# relflow_bed.net
KiCad netlist of a schematic drawn in Altium Designer
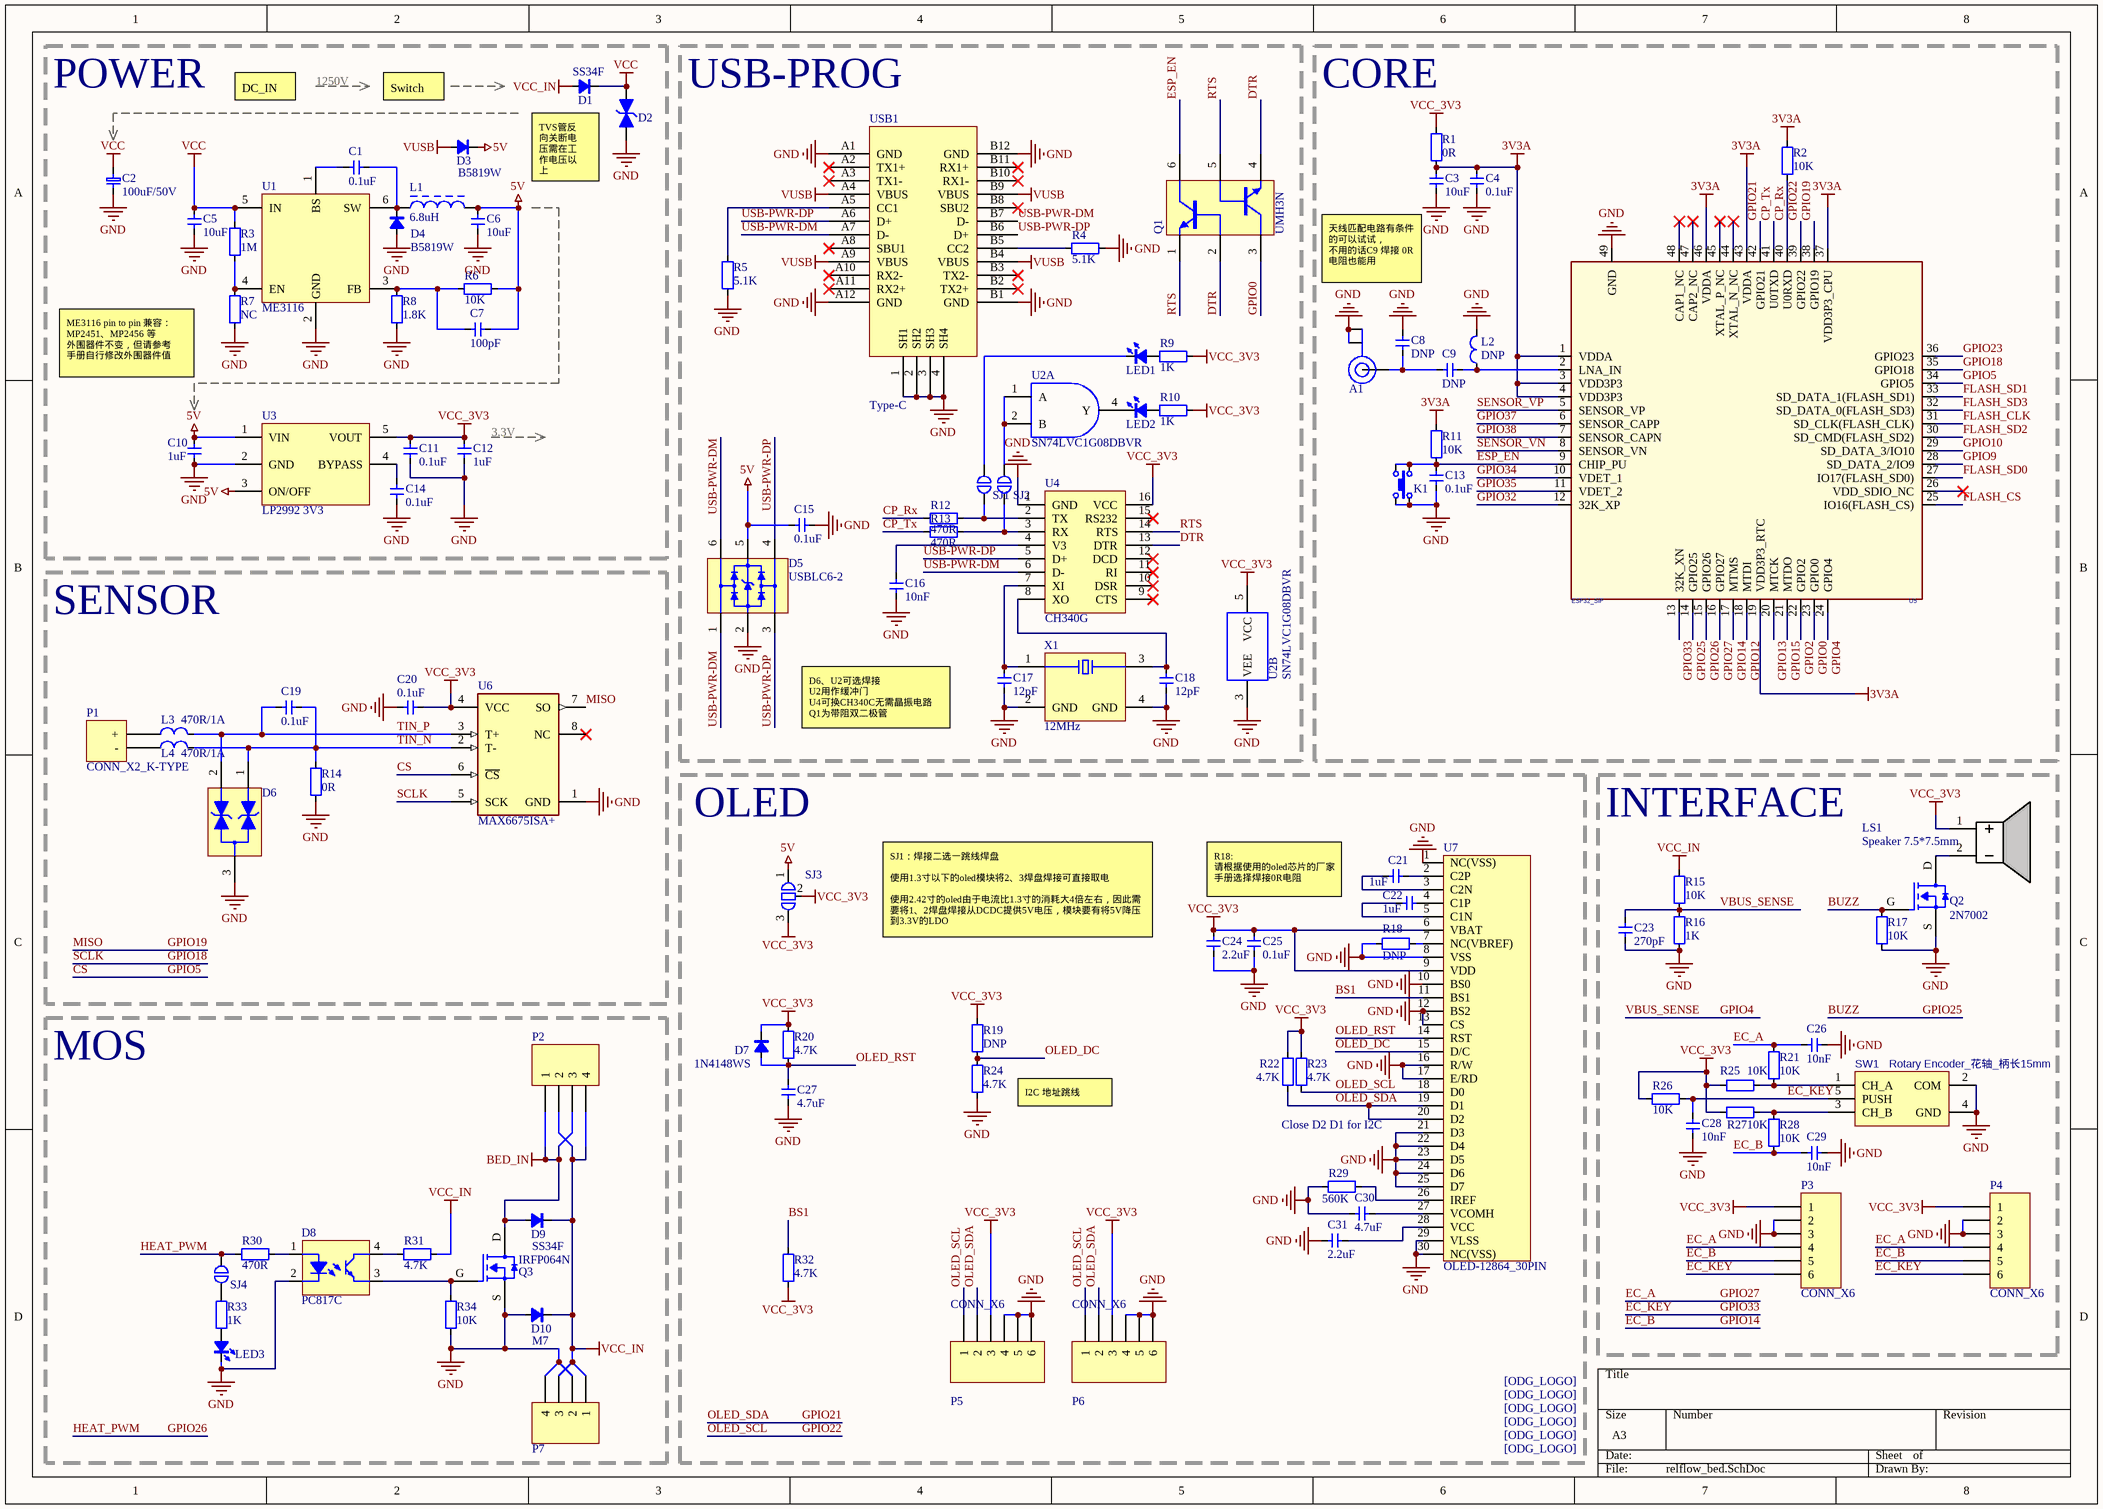
[diagram p0: relflow_bed.SchDoc]

(export (version "E")
  (design (tool "Eeschema 10.0.6"))
  (components
    (comp (ref "*1")
      (value "odg_logo")
      (footprint "odg_logo")
      (libsource (lib "relflow_bed") (part "odg_logo"))
    )
    (comp (ref "*2")
      (value "odg_logo")
      (footprint "odg_logo")
      (libsource (lib "relflow_bed") (part "odg_logo"))
    )
    (comp (ref "*3")
      (value "odg_logo")
      (footprint "odg_logo")
      (libsource (lib "relflow_bed") (part "odg_logo"))
    )
    (comp (ref "*4")
      (value "odg_logo")
      (footprint "odg_logo")
      (libsource (lib "relflow_bed") (part "odg_logo"))
    )
    (comp (ref "*5")
      (value "odg_logo")
      (footprint "odg_logo")
      (libsource (lib "relflow_bed") (part "odg_logo"))
    )
    (comp (ref "*6")
      (value "odg_logo")
      (footprint "odg_logo")
      (libsource (lib "relflow_bed") (part "odg_logo"))
    )
    (comp (ref "A1")
      (value "ANT_IPEX")
      (footprint "IPEX_SMD")
      (libsource (lib "relflow_bed") (part "ANT_IPEX"))
    )
    (comp (ref "C1")
      (value "0.1uF")
      (footprint "C0603")
      (description "Capacitor")
      (libsource (lib "relflow_bed") (part "CAP"))
    )
    (comp (ref "C2")
      (value "100uF/50V")
      (footprint "PANASONIC_E")
      (description "Capacitor")
      (libsource (lib "relflow_bed") (part "CAP_Polar"))
    )
    (comp (ref "C3")
      (value "10uF")
      (footprint "C0603")
      (description "Capacitor")
      (libsource (lib "relflow_bed") (part "CAP"))
    )
    (comp (ref "C4")
      (value "0.1uF")
      (footprint "C0603")
      (description "Capacitor")
      (libsource (lib "relflow_bed") (part "CAP"))
    )
    (comp (ref "C5")
      (value "10uF")
      (footprint "C1206")
      (description "Capacitor")
      (libsource (lib "relflow_bed") (part "CAP"))
    )
    (comp (ref "C6")
      (value "10uF")
      (footprint "C0805")
      (description "Capacitor")
      (libsource (lib "relflow_bed") (part "CAP"))
    )
    (comp (ref "C7")
      (value "100pF")
      (footprint "C0603")
      (description "Capacitor")
      (libsource (lib "relflow_bed") (part "CAP"))
    )
    (comp (ref "C8")
      (value "DNP")
      (footprint "C0603")
      (description "Capacitor")
      (libsource (lib "relflow_bed") (part "CAP"))
    )
    (comp (ref "C9")
      (value "DNP")
      (footprint "C0603")
      (description "Capacitor")
      (libsource (lib "relflow_bed") (part "CAP"))
    )
    (comp (ref "C10")
      (value "1uF")
      (footprint "C0603")
      (description "Capacitor")
      (libsource (lib "relflow_bed") (part "CAP"))
    )
    (comp (ref "C11")
      (value "0.1uF")
      (footprint "C0603")
      (description "Capacitor")
      (libsource (lib "relflow_bed") (part "CAP"))
    )
    (comp (ref "C12")
      (value "1uF")
      (footprint "C0603")
      (description "Capacitor")
      (libsource (lib "relflow_bed") (part "CAP"))
    )
    (comp (ref "C13")
      (value "0.1uF")
      (footprint "C0603")
      (description "Capacitor")
      (libsource (lib "relflow_bed") (part "CAP"))
    )
    (comp (ref "C14")
      (value "0.1uF")
      (footprint "C0603")
      (description "Capacitor")
      (libsource (lib "relflow_bed") (part "CAP"))
    )
    (comp (ref "C15")
      (value "0.1uF")
      (footprint "C0603")
      (description "Capacitor")
      (libsource (lib "relflow_bed") (part "CAP"))
    )
    (comp (ref "C16")
      (value "10nF")
      (footprint "C0603")
      (description "Capacitor")
      (libsource (lib "relflow_bed") (part "CAP"))
    )
    (comp (ref "C17")
      (value "12pF")
      (footprint "C0603")
      (description "Capacitor")
      (libsource (lib "relflow_bed") (part "CAP"))
    )
    (comp (ref "C18")
      (value "12pF")
      (footprint "C0603")
      (description "Capacitor")
      (libsource (lib "relflow_bed") (part "CAP"))
    )
    (comp (ref "C19")
      (value "0.1uF")
      (footprint "C0603")
      (description "Capacitor")
      (libsource (lib "relflow_bed") (part "CAP"))
    )
    (comp (ref "C20")
      (value "0.1uF")
      (footprint "C0603")
      (description "Capacitor")
      (libsource (lib "relflow_bed") (part "CAP"))
    )
    (comp (ref "C21")
      (value "1uF")
      (footprint "C0603")
      (description "Capacitor")
      (libsource (lib "relflow_bed") (part "CAP"))
    )
    (comp (ref "C22")
      (value "1uF")
      (footprint "C0603")
      (description "Capacitor")
      (libsource (lib "relflow_bed") (part "CAP"))
    )
    (comp (ref "C23")
      (value "270pF")
      (footprint "C0603")
      (description "Capacitor")
      (libsource (lib "relflow_bed") (part "CAP"))
    )
    (comp (ref "C24")
      (value "2.2uF")
      (footprint "C0603")
      (description "Capacitor")
      (libsource (lib "relflow_bed") (part "CAP"))
    )
    (comp (ref "C25")
      (value "0.1uF")
      (footprint "C0603")
      (description "Capacitor")
      (libsource (lib "relflow_bed") (part "CAP"))
    )
    (comp (ref "C26")
      (value "10nF")
      (footprint "C0603")
      (description "Capacitor")
      (libsource (lib "relflow_bed") (part "CAP"))
    )
    (comp (ref "C27")
      (value "4.7uF")
      (footprint "C0603")
      (description "Capacitor")
      (libsource (lib "relflow_bed") (part "CAP"))
    )
    (comp (ref "C28")
      (value "10nF")
      (footprint "C0603")
      (description "Capacitor")
      (libsource (lib "relflow_bed") (part "CAP"))
    )
    (comp (ref "C29")
      (value "10nF")
      (footprint "C0603")
      (description "Capacitor")
      (libsource (lib "relflow_bed") (part "CAP"))
    )
    (comp (ref "C30")
      (value "4.7uF")
      (footprint "C0603")
      (description "Capacitor")
      (libsource (lib "relflow_bed") (part "CAP"))
    )
    (comp (ref "C31")
      (value "2.2uF")
      (footprint "C0603")
      (description "Capacitor")
      (libsource (lib "relflow_bed") (part "CAP"))
    )
    (comp (ref "D1") (value "SS34F") (footprint "SMAF") (libsource (lib "") (part "DIODE_1")))
    (comp (ref "D2")
      (value "TVS_Bi")
      (footprint "DO-214AA_SMBJ")
      (libsource (lib "relflow_bed") (part "TVS_Bi"))
    )
    (comp (ref "D3") (value "B5819W") (footprint "SOD-123") (libsource (lib "") (part "DIODE_1")))
    (comp (ref "D4") (value "B5819W") (footprint "SOD-123") (libsource (lib "relflow_bed") (part "DIODE")))
    (comp (ref "D5")
      (value "USBLC6-2")
      (footprint "MICROCHIP SOT-23-6 M6")
      (description "Very low capacitance ESD protection")
      (libsource (lib "relflow_bed") (part "USBLC6-2"))
    )
    (comp (ref "D6")
      (value "NUP2105L")
      (footprint "INFINEON SOT-23-3")
      (libsource (lib "relflow_bed") (part "NUP2105L"))
    )
    (comp (ref "D7") (value "1N4148WS") (footprint "SOD-323") (libsource (lib "relflow_bed") (part "DIODE")))
    (comp (ref "D8")
      (value "PC817C")
      (footprint "DIP-4_SMD")
      (libsource (lib "relflow_bed") (part "Optoisolator"))
    )
    (comp (ref "D9") (value "SS34F") (footprint "SMAF") (libsource (lib "") (part "DIODE_1")))
    (comp (ref "D10") (value "M7") (footprint "SMAF") (libsource (lib "") (part "DIODE_1")))
    (comp (ref "K1")
      (value "~")
      (footprint "TACTILE_SWITCH_SMD_4X4MM")
      (description "Button")
      (libsource (lib "relflow_bed") (part "ButtonTACT"))
    )
    (comp (ref "L1")
      (value "6.8uH")
      (footprint "IND-30301X")
      (libsource (lib "relflow_bed") (part "Inductor"))
    )
    (comp (ref "L2") (value "DNP") (footprint "L0603") (libsource (lib "relflow_bed") (part "FUSE")))
    (comp (ref "L3") (value "470R/1A") (footprint "L0603") (libsource (lib "relflow_bed") (part "FUSE")))
    (comp (ref "L4") (value "470R/1A") (footprint "L0603") (libsource (lib "relflow_bed") (part "FUSE")))
    (comp (ref "LED1") (value "LED") (footprint "LED 0603_1608") (libsource (lib "relflow_bed") (part "LED")))
    (comp (ref "LED2") (value "LED") (footprint "LED 0603_1608") (libsource (lib "relflow_bed") (part "LED")))
    (comp (ref "LED3") (value "LED") (footprint "LED 0603_1608") (libsource (lib "relflow_bed") (part "LED")))
    (comp (ref "LS1")
      (value "Speaker 7.5*7.5mm")
      (footprint "BUZZER_7525")
      (description "Speaker")
      (libsource (lib "relflow_bed") (part "Speaker"))
    )
    (comp (ref "P1")
      (value "CONN_X2_K-TYPE")
      (footprint "K型热电偶连接器母座")
      (libsource (lib "relflow_bed") (part "CONN_X2_K-TYPE"))
    )
    (comp (ref "P2") (value "CONN_X4") (footprint "5569_4P_HOR_90") (libsource (lib "") (part "CONN_X4_1")))
    (comp (ref "P3")
      (value "CONN_X6")
      (footprint "简易牛角座直插_2x3P")
      (libsource (lib "relflow_bed") (part "CONN_X6"))
    )
    (comp (ref "P4")
      (value "CONN_X6")
      (footprint "简易牛角座直插_2x3P")
      (libsource (lib "relflow_bed") (part "CONN_X6"))
    )
    (comp (ref "P5") (value "CONN_X6") (footprint "简易牛角座直插_2x3P") (libsource (lib "") (part "CONN_X6_1")))
    (comp (ref "P6") (value "CONN_X6") (footprint "简易牛角座直插_2x3P") (libsource (lib "") (part "CONN_X6_1")))
    (comp (ref "P7")
      (value "CONN_X4")
      (footprint "5566_4P_VEC")
      (libsource (lib "relflow_bed") (part "CONN_X4"))
    )
    (comp (ref "Q1")
      (value "UMH3N")
      (footprint "ON SEMI SOT-363")
      (description "NPN型带阻双三极管\r\nNPN+NPN, SOT-363, Dual Digital Transistor (Bias Resistor Built-in Transistor)")
      (libsource (lib "relflow_bed") (part "UMH3N"))
    )
    (comp (ref "Q2")
      (value "2N7002")
      (footprint "INFINEON SOT-23-3")
      (description "N-MOS")
      (libsource (lib "relflow_bed") (part "N-MOS"))
    )
    (comp (ref "Q3")
      (value "IRFP064N")
      (footprint "TO-247AC+HEAT_SINK-TO220")
      (description "N-MOS")
      (libsource (lib "relflow_bed") (part "N-MOS"))
    )
    (comp (ref "R1")
      (value "0R")
      (footprint "R0603")
      (description "Resistor")
      (libsource (lib "relflow_bed") (part "RES"))
    )
    (comp (ref "R2")
      (value "10K")
      (footprint "R0603")
      (description "Resistor")
      (libsource (lib "") (part "RES_2"))
    )
    (comp (ref "R3")
      (value "1M")
      (footprint "R0603")
      (description "Resistor")
      (libsource (lib "relflow_bed") (part "RES"))
    )
    (comp (ref "R4")
      (value "5.1K")
      (footprint "R0603")
      (description "Resistor")
      (libsource (lib "") (part "RES_1"))
    )
    (comp (ref "R5")
      (value "5.1K")
      (footprint "R0603")
      (description "Resistor")
      (libsource (lib "relflow_bed") (part "RES"))
    )
    (comp (ref "R6")
      (value "10K")
      (footprint "R0603")
      (description "Resistor")
      (libsource (lib "") (part "RES_1"))
    )
    (comp (ref "R7")
      (value "NC")
      (footprint "R0603")
      (description "Resistor")
      (libsource (lib "relflow_bed") (part "RES"))
    )
    (comp (ref "R8")
      (value "1.8K")
      (footprint "R0603")
      (description "Resistor")
      (libsource (lib "") (part "RES_2"))
    )
    (comp (ref "R9")
      (value "1K")
      (footprint "R0603")
      (description "Resistor")
      (libsource (lib "") (part "RES_1"))
    )
    (comp (ref "R10")
      (value "1K")
      (footprint "R0603")
      (description "Resistor")
      (libsource (lib "") (part "RES_1"))
    )
    (comp (ref "R11")
      (value "10K")
      (footprint "R0603")
      (description "Resistor")
      (libsource (lib "relflow_bed") (part "RES"))
    )
    (comp (ref "R12")
      (value "470R")
      (footprint "R0603")
      (description "Resistor")
      (libsource (lib "") (part "RES_2"))
    )
    (comp (ref "R13")
      (value "470R")
      (footprint "R0603")
      (description "Resistor")
      (libsource (lib "") (part "RES_2"))
    )
    (comp (ref "R14")
      (value "0R")
      (footprint "R0603")
      (description "Resistor")
      (libsource (lib "") (part "RES_1"))
    )
    (comp (ref "R15")
      (value "10K")
      (footprint "R0603")
      (description "Resistor")
      (libsource (lib "relflow_bed") (part "RES"))
    )
    (comp (ref "R16")
      (value "1K")
      (footprint "R0603")
      (description "Resistor")
      (libsource (lib "relflow_bed") (part "RES"))
    )
    (comp (ref "R17")
      (value "10K")
      (footprint "R0603")
      (description "Resistor")
      (libsource (lib "") (part "RES_2"))
    )
    (comp (ref "R18")
      (value "DNP")
      (footprint "R0603")
      (description "Resistor")
      (libsource (lib "") (part "RES_1"))
    )
    (comp (ref "R19")
      (value "DNP")
      (footprint "R0603")
      (description "Resistor")
      (libsource (lib "") (part "RES_3"))
    )
    (comp (ref "R20")
      (value "4.7K")
      (footprint "R0603")
      (description "Resistor")
      (libsource (lib "") (part "RES_2"))
    )
    (comp (ref "R21")
      (value "10K")
      (footprint "R0603")
      (description "Resistor")
      (libsource (lib "relflow_bed") (part "RES"))
    )
    (comp (ref "R22")
      (value "4.7K")
      (footprint "R0603")
      (description "Resistor")
      (libsource (lib "relflow_bed") (part "RES"))
    )
    (comp (ref "R23")
      (value "4.7K")
      (footprint "R0603")
      (description "Resistor")
      (libsource (lib "relflow_bed") (part "RES"))
    )
    (comp (ref "R24")
      (value "4.7K")
      (footprint "R0603")
      (description "Resistor")
      (libsource (lib "") (part "RES_3"))
    )
    (comp (ref "R25")
      (value "10K")
      (footprint "R0603")
      (description "Resistor")
      (libsource (lib "") (part "RES_1"))
    )
    (comp (ref "R26")
      (value "10K")
      (footprint "R0603")
      (description "Resistor")
      (libsource (lib "") (part "RES_1"))
    )
    (comp (ref "R27")
      (value "10K")
      (footprint "R0603")
      (description "Resistor")
      (libsource (lib "") (part "RES_1"))
    )
    (comp (ref "R28")
      (value "10K")
      (footprint "R0603")
      (description "Resistor")
      (libsource (lib "relflow_bed") (part "RES"))
    )
    (comp (ref "R29")
      (value "560K")
      (footprint "R0603")
      (description "Resistor")
      (libsource (lib "") (part "RES_3"))
    )
    (comp (ref "R30")
      (value "470R")
      (footprint "R0603")
      (description "Resistor")
      (libsource (lib "relflow_bed") (part "RES"))
    )
    (comp (ref "R31")
      (value "4.7K")
      (footprint "R0603")
      (description "Resistor")
      (libsource (lib "relflow_bed") (part "RES"))
    )
    (comp (ref "R32")
      (value "4.7K")
      (footprint "R0603")
      (description "Resistor")
      (libsource (lib "") (part "RES_2"))
    )
    (comp (ref "R33")
      (value "1K")
      (footprint "R0603")
      (description "Resistor")
      (libsource (lib "") (part "RES_1"))
    )
    (comp (ref "R34")
      (value "10K")
      (footprint "R0603")
      (description "Resistor")
      (libsource (lib "") (part "RES_2"))
    )
    (comp (ref "SJ1") (value "SJ_2P") (footprint "SJ_2P_MINI") (libsource (lib "relflow_bed") (part "SJ_2P")))
    (comp (ref "SJ2") (value "SJ_2P") (footprint "SJ_2P_MINI") (libsource (lib "relflow_bed") (part "SJ_2P")))
    (comp (ref "SJ3") (value "SJ_3P") (footprint "SJ_3P") (libsource (lib "relflow_bed") (part "SJ_3P")))
    (comp (ref "SJ4") (value "SJ_2P") (footprint "SJ_2P_MINI") (libsource (lib "relflow_bed") (part "SJ_2P")))
    (comp (ref "SW1")
      (value "Rotary Encoder_花轴_柄长15mm")
      (footprint "ENCODER-1")
      (libsource (lib "relflow_bed") (part "Rotary Encoder"))
    )
    (comp (ref "U1")
      (value "ME3116")
      (footprint "MICROCHIP SOT-23-6 M6")
      (description "DC-DC")
      (libsource (lib "relflow_bed") (part "ME3116"))
    )
    (comp (ref "U2")
      (value "SN74LVC1G08DBVR")
      (footprint "MICROCHIP SOT-23-5 OT")
      (description "Single 2-input AND gate\r\n1.8~3.3V logic")
      (libsource (lib "relflow_bed") (part "SN74LVC1G08DBVR"))
    )
    (comp (ref "U3")
      (value "LP2992 3V3")
      (footprint "MICROCHIP SOT-23-5 OT")
      (description "LDO")
      (libsource (lib "relflow_bed") (part "LP2992"))
    )
    (comp (ref "U4")
      (value "CH340G")
      (footprint "TI SOP-16 D")
      (description "丐中丐，需要外接12M晶振")
      (libsource (lib "relflow_bed") (part "CH340G"))
    )
    (comp (ref "U5")
      (value "ESP32_SIP")
      (footprint "QFN-48_7X7_via")
      (libsource (lib "relflow_bed") (part "ESP32-PICO"))
    )
    (comp (ref "U6")
      (value "MAX6675ISA")
      (footprint "SO-8")
      (description "IC THERMOCOUP TO DGTL 8-SOIC")
      (fields
        (field (name "MANUFACTURER") "Maxim Electronics")
        (field (name "OCTOPART PART NUMBER") "33bcfab92ad8ec7b")
        (field (name "PART NUMBER") "MAX6675ISA+")
      )
      (libsource (lib "OpenHeat") (part "MAX6675ISA"))
    )
    (comp (ref "U7")
      (value "OLED-12864_30PIN")
      (footprint "UG-2864HSWEG01_1.29_SSD1315_BUTTOM")
      (description "显示屏")
      (libsource (lib "relflow_bed") (part "OLED-12864_30PIN"))
    )
    (comp (ref "USB1")
      (value "Type-C")
      (footprint "Type-C-TOP")
      (libsource (lib "relflow_bed") (part "USB-Type-C-24P"))
    )
    (comp (ref "X1")
      (value "12MHz")
      (footprint "EPSON TSX-3225")
      (description "4脚无源晶振")
      (libsource (lib "relflow_bed") (part "XTAL-4P"))
    )
  )
  (nets
    (net (code "1") (name "/BS1") (class "Default")
      (node (ref "R32") (pin "2") (pinfunction "2_2") (pintype "passive"))
      (node (ref "U7") (pin "11") (pinfunction "BS1_11") (pintype "passive"))
    )
    (net (code "2") (name "/BUZZ") (class "Default")
      (node (ref "Q2") (pin "G") (pinfunction "G_G") (pintype "passive"))
      (node (ref "R17") (pin "2") (pinfunction "2_2") (pintype "passive"))
      (node (ref "U5") (pin "14") (pinfunction "GPIO25_14") (pintype "passive"))
    )
    (net (code "3") (name "/CP_Rx") (class "Default")
      (node (ref "R12") (pin "1") (pinfunction "1_1") (pintype "passive"))
      (node (ref "R2") (pin "1") (pinfunction "1_1") (pintype "passive"))
      (node (ref "U5") (pin "40") (pinfunction "U0RXD_40") (pintype "power_in"))
    )
    (net (code "4") (name "/CP_Tx") (class "Default")
      (node (ref "R13") (pin "1") (pinfunction "1_1") (pintype "passive"))
      (node (ref "U5") (pin "41") (pinfunction "U0TXD_41") (pintype "power_in"))
    )
    (net (code "5") (name "/CS") (class "Default")
      (node (ref "U5") (pin "34") (pinfunction "GPIO5_34") (pintype "passive"))
      (node (ref "U6") (pin "6") (pinfunction "~{CS}_6") (pintype "input"))
    )
    (net (code "6") (name "/DTR") (class "Default")
      (node (ref "Q1") (pin "2") (pinfunction "B_2") (pintype "passive"))
      (node (ref "Q1") (pin "4") (pinfunction "E_4") (pintype "passive"))
      (node (ref "U4") (pin "13") (pinfunction "DTR_13") (pintype "passive"))
    )
    (net (code "7") (name "/EC_A") (class "Default")
      (node (ref "C26") (pin "2") (pinfunction "2_2") (pintype "passive"))
      (node (ref "P3") (pin "4") (pinfunction "4_4") (pintype "passive"))
      (node (ref "P4") (pin "4") (pinfunction "4_4") (pintype "passive"))
      (node (ref "R21") (pin "1") (pinfunction "1_1") (pintype "passive"))
      (node (ref "U5") (pin "16") (pinfunction "GPIO27_16") (pintype "passive"))
    )
    (net (code "8") (name "/EC_B") (class "Default")
      (node (ref "C29") (pin "2") (pinfunction "2_2") (pintype "passive"))
      (node (ref "P3") (pin "5") (pinfunction "5_5") (pintype "passive"))
      (node (ref "P4") (pin "5") (pinfunction "5_5") (pintype "passive"))
      (node (ref "R28") (pin "2") (pinfunction "2_2") (pintype "passive"))
      (node (ref "U5") (pin "17") (pinfunction "MTMS_17") (pintype "passive"))
    )
    (net (code "9") (name "/EC_KEY") (class "Default")
      (node (ref "C28") (pin "2") (pinfunction "2_2") (pintype "passive"))
      (node (ref "P3") (pin "6") (pinfunction "6_6") (pintype "passive"))
      (node (ref "P4") (pin "6") (pinfunction "6_6") (pintype "passive"))
      (node (ref "R26") (pin "1") (pinfunction "1_1") (pintype "passive"))
      (node (ref "SW1") (pin "5") (pinfunction "PUSH_5") (pintype "passive"))
      (node (ref "U5") (pin "13") (pinfunction "32K_XN_13") (pintype "passive"))
    )
    (net (code "10") (name "/ESP_EN") (class "Default")
      (node (ref "C13") (pin "1") (pinfunction "1_1") (pintype "passive"))
      (node (ref "K1") (pin "3") (pinfunction "3_3") (pintype "passive"))
      (node (ref "K1") (pin "4") (pinfunction "4_4") (pintype "passive"))
      (node (ref "Q1") (pin "6") (pinfunction "C_6") (pintype "passive"))
      (node (ref "R11") (pin "2") (pinfunction "2_2") (pintype "passive"))
      (node (ref "U5") (pin "9") (pinfunction "CHIP_PU_9") (pintype "passive"))
    )
    (net (code "11") (name "/FLASH_CLK") (class "Default")
      (node (ref "U5") (pin "31") (pinfunction "SD_CLK(FLASH_CLK)_31") (pintype "passive"))
    )
    (net (code "12") (name "/FLASH_CS") (class "Default")
      (node (ref "U5") (pin "25") (pinfunction "IO16(FLASH_CS)_25") (pintype "passive"))
    )
    (net (code "13") (name "/FLASH_SD0") (class "Default")
      (node (ref "U5") (pin "27") (pinfunction "IO17(FLASH_SD0)_27") (pintype "passive"))
    )
    (net (code "14") (name "/FLASH_SD1") (class "Default")
      (node (ref "U5") (pin "33") (pinfunction "SD_DATA_1(FLASH_SD1)_33") (pintype "passive"))
    )
    (net (code "15") (name "/FLASH_SD2") (class "Default")
      (node (ref "U5") (pin "30") (pinfunction "SD_CMD(FLASH_SD2)_30") (pintype "passive"))
    )
    (net (code "16") (name "/FLASH_SD3") (class "Default")
      (node (ref "U5") (pin "32") (pinfunction "SD_DATA_0(FLASH_SD3)_32") (pintype "passive"))
    )
    (net (code "17") (name "/GPIO0") (class "Default")
      (node (ref "Q1") (pin "3") (pinfunction "C_3") (pintype "passive"))
      (node (ref "U5") (pin "23") (pinfunction "GPIO0_23") (pintype "passive"))
    )
    (net (code "18") (name "/GPIO2") (class "Default")
      (node (ref "U5") (pin "22") (pinfunction "GPIO2_22") (pintype "passive"))
    )
    (net (code "19") (name "/GPIO4") (class "Default")
      (node (ref "C23") (pin "2") (pinfunction "2_2") (pintype "passive"))
      (node (ref "R15") (pin "2") (pinfunction "2_2") (pintype "passive"))
      (node (ref "R16") (pin "1") (pinfunction "1_1") (pintype "passive"))
      (node (ref "U5") (pin "24") (pinfunction "GPIO4_24") (pintype "passive"))
    )
    (net (code "20") (name "/GPIO9") (class "Default")
      (node (ref "U5") (pin "28") (pinfunction "SD_DATA_2/IO9_28") (pintype "passive"))
    )
    (net (code "21") (name "/GPIO10") (class "Default")
      (node (ref "U5") (pin "29") (pinfunction "SD_DATA_3/IO10_29") (pintype "passive"))
    )
    (net (code "22") (name "/GPIO12") (class "Default")
      (node (ref "U5") (pin "18") (pinfunction "MTDI_18") (pintype "passive"))
    )
    (net (code "23") (name "/GPIO13") (class "Default")
      (node (ref "U5") (pin "20") (pinfunction "MTCK_20") (pintype "passive"))
    )
    (net (code "24") (name "/GPIO15") (class "Default")
      (node (ref "U5") (pin "21") (pinfunction "MTDO_21") (pintype "passive"))
    )
    (net (code "25") (name "/GPIO18") (class "Default")
      (node (ref "U5") (pin "35") (pinfunction "GPIO18_35") (pintype "passive"))
      (node (ref "U6") (pin "5") (pinfunction "SCK_5") (pintype "input"))
    )
    (net (code "26") (name "/GPIO19") (class "Default")
      (node (ref "U5") (pin "38") (pinfunction "GPIO19_38") (pintype "passive"))
      (node (ref "U6") (pin "7") (pinfunction "SO_7") (pintype "output"))
    )
    (net (code "27") (name "/GPIO21") (class "Default")
      (node (ref "P5") (pin "2") (pinfunction "2_2") (pintype "passive"))
      (node (ref "P6") (pin "2") (pinfunction "2_2") (pintype "passive"))
      (node (ref "R22") (pin "2") (pinfunction "2_2") (pintype "passive"))
      (node (ref "U5") (pin "42") (pinfunction "GPIO21_42") (pintype "passive"))
      (node (ref "U7") (pin "19") (pinfunction "D1_19") (pintype "passive"))
      (node (ref "U7") (pin "20") (pinfunction "D2_20") (pintype "passive"))
    )
    (net (code "28") (name "/GPIO22") (class "Default")
      (node (ref "P5") (pin "1") (pinfunction "1_1") (pintype "passive"))
      (node (ref "P6") (pin "1") (pinfunction "1_1") (pintype "passive"))
      (node (ref "R23") (pin "2") (pinfunction "2_2") (pintype "passive"))
      (node (ref "U5") (pin "39") (pinfunction "GPIO22_39") (pintype "passive"))
      (node (ref "U7") (pin "18") (pinfunction "D0_18") (pintype "passive"))
    )
    (net (code "29") (name "/GPIO23") (class "Default")
      (node (ref "U5") (pin "36") (pinfunction "GPIO23_36") (pintype "passive"))
    )
    (net (code "30") (name "/GPIO26") (class "Default")
      (node (ref "R30") (pin "2") (pinfunction "2_2") (pintype "passive"))
      (node (ref "SJ4") (pin "1") (pinfunction "1_1") (pintype "passive"))
      (node (ref "U5") (pin "15") (pinfunction "GPIO26_15") (pintype "passive"))
    )
    (net (code "31") (name "/GPIO32") (class "Default")
      (node (ref "U5") (pin "12") (pinfunction "32K_XP_12") (pintype "passive"))
    )
    (net (code "32") (name "/GPIO34") (class "Default")
      (node (ref "U5") (pin "10") (pinfunction "VDET_1_10") (pintype "passive"))
    )
    (net (code "33") (name "/GPIO35") (class "Default")
      (node (ref "U5") (pin "11") (pinfunction "VDET_2_11") (pintype "passive"))
    )
    (net (code "34") (name "/GPIO37") (class "Default")
      (node (ref "U5") (pin "6") (pinfunction "SENSOR_CAPP_6") (pintype "passive"))
    )
    (net (code "35") (name "/GPIO38") (class "Default")
      (node (ref "U5") (pin "7") (pinfunction "SENSOR_CAPN_7") (pintype "passive"))
    )
    (net (code "36") (name "/OLED_DC") (class "Default")
      (node (ref "R19") (pin "1") (pinfunction "1_1") (pintype "passive"))
      (node (ref "R24") (pin "2") (pinfunction "2_2") (pintype "passive"))
      (node (ref "U7") (pin "15") (pinfunction "D/C_15") (pintype "passive"))
    )
    (net (code "37") (name "/OLED_RST") (class "Default")
      (node (ref "C27") (pin "2") (pinfunction "2_2") (pintype "passive"))
      (node (ref "D7") (pin "1") (pinfunction "A_1") (pintype "passive"))
      (node (ref "R20") (pin "1") (pinfunction "1_1") (pintype "passive"))
      (node (ref "U7") (pin "14") (pinfunction "RST_14") (pintype "passive"))
    )
    (net (code "38") (name "/RTS") (class "Default")
      (node (ref "Q1") (pin "1") (pinfunction "E_1") (pintype "passive"))
      (node (ref "Q1") (pin "5") (pinfunction "B_5") (pintype "passive"))
      (node (ref "U4") (pin "14") (pinfunction "RTS_14") (pintype "passive"))
    )
    (net (code "39") (name "/SENSOR_VN") (class "Default")
      (node (ref "U5") (pin "8") (pinfunction "SENSOR_VN_8") (pintype "passive"))
    )
    (net (code "40") (name "/SENSOR_VP") (class "Default")
      (node (ref "U5") (pin "5") (pinfunction "SENSOR_VP_5") (pintype "passive"))
    )
    (net (code "41") (name "/TIN_N") (class "Default")
      (node (ref "C19") (pin "1") (pinfunction "1_1") (pintype "passive"))
      (node (ref "D6") (pin "1") (pinfunction "1_1") (pintype "passive"))
      (node (ref "L4") (pin "2") (pinfunction "2_2") (pintype "passive"))
      (node (ref "R14") (pin "1") (pinfunction "1_1") (pintype "passive"))
      (node (ref "U6") (pin "2") (pinfunction "T-_2") (pintype "input"))
    )
    (net (code "42") (name "/TIN_P") (class "Default")
      (node (ref "C19") (pin "2") (pinfunction "2_2") (pintype "passive"))
      (node (ref "D6") (pin "2") (pinfunction "2_2") (pintype "passive"))
      (node (ref "L3") (pin "2") (pinfunction "2_2") (pintype "passive"))
      (node (ref "U6") (pin "3") (pinfunction "T+_3") (pintype "input"))
    )
    (net (code "43") (name "/USB-PWR-DM") (class "Default")
      (node (ref "D5") (pin "1") (pinfunction "I/O1_1") (pintype "passive"))
      (node (ref "D5") (pin "6") (pinfunction "I/O1_6") (pintype "passive"))
      (node (ref "U4") (pin "6") (pinfunction "D-_6") (pintype "passive"))
      (node (ref "USB1") (pin "A7") (pinfunction "D-_A7") (pintype "passive"))
      (node (ref "USB1") (pin "B7") (pinfunction "D-_B7") (pintype "passive"))
    )
    (net (code "44") (name "/USB-PWR-DP") (class "Default")
      (node (ref "D5") (pin "3") (pinfunction "I/O2_3") (pintype "passive"))
      (node (ref "D5") (pin "4") (pinfunction "I/O2_4") (pintype "passive"))
      (node (ref "U4") (pin "5") (pinfunction "D+_5") (pintype "passive"))
      (node (ref "USB1") (pin "A6") (pinfunction "D+_A6") (pintype "passive"))
      (node (ref "USB1") (pin "B6") (pinfunction "D+_B6") (pintype "passive"))
    )
    (net (code "45") (name "3V3A") (class "Default")
      (node (ref "C3") (pin "2") (pinfunction "2_2") (pintype "passive"))
      (node (ref "C4") (pin "2") (pinfunction "2_2") (pintype "passive"))
      (node (ref "R1") (pin "2") (pinfunction "2_2") (pintype "passive"))
      (node (ref "R11") (pin "1") (pinfunction "1_1") (pintype "passive"))
      (node (ref "R2") (pin "2") (pinfunction "2_2") (pintype "passive"))
      (node (ref "U5") (pin "1") (pinfunction "VDDA_1") (pintype "power_in"))
      (node (ref "U5") (pin "19") (pinfunction "VDD3P3_RTC_19") (pintype "power_in"))
      (node (ref "U5") (pin "3") (pinfunction "VDD3P3_3") (pintype "power_in"))
      (node (ref "U5") (pin "37") (pinfunction "VDD3P3_CPU_37") (pintype "power_in"))
      (node (ref "U5") (pin "4") (pinfunction "VDD3P3_4") (pintype "power_in"))
      (node (ref "U5") (pin "43") (pinfunction "VDDA_43") (pintype "power_in"))
      (node (ref "U5") (pin "46") (pinfunction "VDDA_46") (pintype "power_in"))
    )
    (net (code "46") (name "5V") (class "Default")
      (node (ref "C10") (pin "2") (pinfunction "2_2") (pintype "passive"))
      (node (ref "C15") (pin "2") (pinfunction "2_2") (pintype "passive"))
      (node (ref "C6") (pin "2") (pinfunction "2_2") (pintype "passive"))
      (node (ref "C7") (pin "2") (pinfunction "2_2") (pintype "passive"))
      (node (ref "D3") (pin "2") (pinfunction "C_2") (pintype "passive"))
      (node (ref "D5") (pin "5") (pinfunction "VBUS_5") (pintype "passive"))
      (node (ref "L1") (pin "2") (pinfunction "2_2") (pintype "passive"))
      (node (ref "R6") (pin "1") (pinfunction "1_1") (pintype "passive"))
      (node (ref "SJ3") (pin "1") (pinfunction "1_1") (pintype "passive"))
      (node (ref "U3") (pin "1") (pinfunction "VIN_1") (pintype "passive"))
      (node (ref "U3") (pin "3") (pinfunction "ON/OFF_3") (pintype "passive"))
    )
    (net (code "47") (name "BED_IN") (class "Default")
      (node (ref "D9") (pin "1") (pinfunction "A_1") (pintype "passive"))
      (node (ref "P2") (pin "1") (pinfunction "1_1") (pintype "passive"))
      (node (ref "P2") (pin "3") (pinfunction "3_3") (pintype "passive"))
      (node (ref "Q3") (pin "D") (pinfunction "D_D") (pintype "passive"))
    )
    (net (code "48") (name "GND") (class "Default")
      (node (ref "A1") (pin "2") (pinfunction "2_2") (pintype "passive"))
      (node (ref "A1") (pin "3") (pinfunction "3_3") (pintype "passive"))
      (node (ref "C10") (pin "1") (pinfunction "1_1") (pintype "passive"))
      (node (ref "C11") (pin "1") (pinfunction "1_1") (pintype "passive"))
      (node (ref "C12") (pin "1") (pinfunction "1_1") (pintype "passive"))
      (node (ref "C13") (pin "2") (pinfunction "2_2") (pintype "passive"))
      (node (ref "C14") (pin "1") (pinfunction "1_1") (pintype "passive"))
      (node (ref "C15") (pin "1") (pinfunction "1_1") (pintype "passive"))
      (node (ref "C16") (pin "1") (pinfunction "1_1") (pintype "passive"))
      (node (ref "C17") (pin "1") (pinfunction "1_1") (pintype "passive"))
      (node (ref "C18") (pin "1") (pinfunction "1_1") (pintype "passive"))
      (node (ref "C2") (pin "2") (pinfunction "2_2") (pintype "passive"))
      (node (ref "C20") (pin "2") (pinfunction "2_2") (pintype "passive"))
      (node (ref "C23") (pin "1") (pinfunction "1_1") (pintype "passive"))
      (node (ref "C24") (pin "1") (pinfunction "1_1") (pintype "passive"))
      (node (ref "C25") (pin "1") (pinfunction "1_1") (pintype "passive"))
      (node (ref "C26") (pin "1") (pinfunction "1_1") (pintype "passive"))
      (node (ref "C27") (pin "1") (pinfunction "1_1") (pintype "passive"))
      (node (ref "C28") (pin "1") (pinfunction "1_1") (pintype "passive"))
      (node (ref "C29") (pin "1") (pinfunction "1_1") (pintype "passive"))
      (node (ref "C3") (pin "1") (pinfunction "1_1") (pintype "passive"))
      (node (ref "C30") (pin "2") (pinfunction "2_2") (pintype "passive"))
      (node (ref "C31") (pin "2") (pinfunction "2_2") (pintype "passive"))
      (node (ref "C4") (pin "1") (pinfunction "1_1") (pintype "passive"))
      (node (ref "C5") (pin "2") (pinfunction "2_2") (pintype "passive"))
      (node (ref "C6") (pin "1") (pinfunction "1_1") (pintype "passive"))
      (node (ref "C8") (pin "2") (pinfunction "2_2") (pintype "passive"))
      (node (ref "D10") (pin "1") (pinfunction "A_1") (pintype "passive"))
      (node (ref "D2") (pin "1") (pinfunction "1_1") (pintype "passive"))
      (node (ref "D4") (pin "1") (pinfunction "A_1") (pintype "passive"))
      (node (ref "D5") (pin "2") (pinfunction "GND_2") (pintype "passive"))
      (node (ref "D6") (pin "3") (pinfunction "3_3") (pintype "passive"))
      (node (ref "D8") (pin "2") (pinfunction "2_2") (pintype "passive"))
      (node (ref "K1") (pin "1") (pinfunction "1_1") (pintype "passive"))
      (node (ref "K1") (pin "2") (pinfunction "2_2") (pintype "passive"))
      (node (ref "L2") (pin "2") (pinfunction "2_2") (pintype "passive"))
      (node (ref "LED3") (pin "2") (pinfunction "K_2") (pintype "passive"))
      (node (ref "P3") (pin "2") (pinfunction "2_2") (pintype "passive"))
      (node (ref "P3") (pin "3") (pinfunction "3_3") (pintype "passive"))
      (node (ref "P4") (pin "2") (pinfunction "2_2") (pintype "passive"))
      (node (ref "P4") (pin "3") (pinfunction "3_3") (pintype "passive"))
      (node (ref "P5") (pin "4") (pinfunction "4_4") (pintype "passive"))
      (node (ref "P5") (pin "5") (pinfunction "5_5") (pintype "passive"))
      (node (ref "P5") (pin "6") (pinfunction "6_6") (pintype "passive"))
      (node (ref "P6") (pin "4") (pinfunction "4_4") (pintype "passive"))
      (node (ref "P6") (pin "5") (pinfunction "5_5") (pintype "passive"))
      (node (ref "P6") (pin "6") (pinfunction "6_6") (pintype "passive"))
      (node (ref "P7") (pin "2") (pinfunction "2_2") (pintype "passive"))
      (node (ref "P7") (pin "4") (pinfunction "4_4") (pintype "passive"))
      (node (ref "Q2") (pin "S") (pinfunction "S_S") (pintype "passive"))
      (node (ref "Q3") (pin "S") (pinfunction "S_S") (pintype "passive"))
      (node (ref "R14") (pin "2") (pinfunction "2_2") (pintype "passive"))
      (node (ref "R16") (pin "2") (pinfunction "2_2") (pintype "passive"))
      (node (ref "R17") (pin "1") (pinfunction "1_1") (pintype "passive"))
      (node (ref "R18") (pin "2") (pinfunction "2_2") (pintype "passive"))
      (node (ref "R24") (pin "1") (pinfunction "1_1") (pintype "passive"))
      (node (ref "R29") (pin "1") (pinfunction "1_1") (pintype "passive"))
      (node (ref "R34") (pin "1") (pinfunction "1_1") (pintype "passive"))
      (node (ref "R4") (pin "1") (pinfunction "1_1") (pintype "passive"))
      (node (ref "R5") (pin "2") (pinfunction "2_2") (pintype "passive"))
      (node (ref "R7") (pin "2") (pinfunction "2_2") (pintype "passive"))
      (node (ref "R8") (pin "1") (pinfunction "1_1") (pintype "passive"))
      (node (ref "SW1") (pin "2") (pinfunction "COM_2") (pintype "passive"))
      (node (ref "SW1") (pin "4") (pinfunction "GND_4") (pintype "passive"))
      (node (ref "U1") (pin "2") (pinfunction "GND_2") (pintype "passive"))
      (node (ref "U2") (pin "3") (pinfunction "VEE_3") (pintype "passive"))
      (node (ref "U3") (pin "2") (pinfunction "GND_2") (pintype "passive"))
      (node (ref "U4") (pin "1") (pinfunction "GND_1") (pintype "passive"))
      (node (ref "U5") (pin "49") (pinfunction "GND_49") (pintype "power_in"))
      (node (ref "U6") (pin "1") (pinfunction "GND_1") (pintype "power_in"))
      (node (ref "U7") (pin "1") (pinfunction "NC(VSS)_1") (pintype "passive"))
      (node (ref "U7") (pin "10") (pinfunction "BS0_10") (pintype "passive"))
      (node (ref "U7") (pin "12") (pinfunction "BS2_12") (pintype "passive"))
      (node (ref "U7") (pin "13") (pinfunction "CS_13") (pintype "passive"))
      (node (ref "U7") (pin "16") (pinfunction "R/W_16") (pintype "passive"))
      (node (ref "U7") (pin "17") (pinfunction "E/RD_17") (pintype "passive"))
      (node (ref "U7") (pin "21") (pinfunction "D3_21") (pintype "passive"))
      (node (ref "U7") (pin "22") (pinfunction "D4_22") (pintype "passive"))
      (node (ref "U7") (pin "23") (pinfunction "D5_23") (pintype "passive"))
      (node (ref "U7") (pin "24") (pinfunction "D6_24") (pintype "passive"))
      (node (ref "U7") (pin "25") (pinfunction "D7_25") (pintype "passive"))
      (node (ref "U7") (pin "29") (pinfunction "VLSS_29") (pintype "passive"))
      (node (ref "U7") (pin "30") (pinfunction "NC(VSS)_30") (pintype "passive"))
      (node (ref "U7") (pin "8") (pinfunction "VSS_8") (pintype "passive"))
      (node (ref "USB1") (pin "1") (pinfunction "SH1_1") (pintype "passive"))
      (node (ref "USB1") (pin "2") (pinfunction "SH2_2") (pintype "passive"))
      (node (ref "USB1") (pin "3") (pinfunction "SH3_3") (pintype "passive"))
      (node (ref "USB1") (pin "4") (pinfunction "SH4_4") (pintype "passive"))
      (node (ref "USB1") (pin "A1") (pinfunction "GND_A1") (pintype "passive"))
      (node (ref "USB1") (pin "A12") (pinfunction "GND_A12") (pintype "passive"))
      (node (ref "USB1") (pin "B1") (pinfunction "GND_B1") (pintype "passive"))
      (node (ref "USB1") (pin "B12") (pinfunction "GND_B12") (pintype "passive"))
      (node (ref "X1") (pin "2") (pinfunction "GND_2") (pintype "passive"))
      (node (ref "X1") (pin "4") (pinfunction "GND_4") (pintype "passive"))
    )
    (net (code "49") (name "Net-(A1-Pad1)") (class "Default")
      (node (ref "A1") (pin "1") (pinfunction "1_1") (pintype "passive"))
      (node (ref "C8") (pin "1") (pinfunction "1_1") (pintype "passive"))
      (node (ref "C9") (pin "1") (pinfunction "1_1") (pintype "passive"))
    )
    (net (code "50") (name "Net-(D4-C)") (class "Default")
      (node (ref "C1") (pin "1") (pinfunction "1_1") (pintype "passive"))
      (node (ref "D4") (pin "2") (pinfunction "C_2") (pintype "passive"))
      (node (ref "L1") (pin "1") (pintype "passive"))
      (node (ref "U1") (pin "6") (pinfunction "SW_6") (pintype "passive"))
    )
    (net (code "51") (name "Net-(D8-Pad1)") (class "Default")
      (node (ref "D8") (pin "1") (pinfunction "1_1") (pintype "passive"))
      (node (ref "R30") (pin "1") (pinfunction "1_1") (pintype "passive"))
    )
    (net (code "52") (name "Net-(D8-Pad3)") (class "Default")
      (node (ref "D8") (pin "3") (pinfunction "3_3") (pintype "passive"))
      (node (ref "Q3") (pin "G") (pinfunction "G_G") (pintype "passive"))
      (node (ref "R34") (pin "2") (pinfunction "2_2") (pintype "passive"))
    )
    (net (code "53") (name "Net-(D8-Pad4)") (class "Default")
      (node (ref "D8") (pin "4") (pinfunction "4_4") (pintype "passive"))
      (node (ref "R31") (pin "2") (pinfunction "2_2") (pintype "passive"))
    )
    (net (code "54") (name "Net-(L3-Pad1)") (class "Default")
      (node (ref "L3") (pin "1") (pinfunction "1_1") (pintype "passive"))
      (node (ref "P1") (pin "+") (pinfunction "+_+") (pintype "passive"))
    )
    (net (code "55") (name "Net-(L4-Pad1)") (class "Default")
      (node (ref "L4") (pin "1") (pinfunction "1_1") (pintype "passive"))
      (node (ref "P1") (pin "-") (pinfunction "-_-") (pintype "passive"))
    )
    (net (code "56") (name "Net-(LED1-A)") (class "Default")
      (node (ref "LED1") (pin "1") (pinfunction "A_1") (pintype "passive"))
      (node (ref "R9") (pin "2") (pinfunction "2_2") (pintype "passive"))
    )
    (net (code "57") (name "Net-(LED1-K)") (class "Default")
      (node (ref "LED1") (pin "2") (pinfunction "K_2") (pintype "passive"))
      (node (ref "SJ1") (pin "1") (pinfunction "1_1") (pintype "passive"))
    )
    (net (code "58") (name "Net-(LED2-A)") (class "Default")
      (node (ref "LED2") (pin "1") (pinfunction "A_1") (pintype "passive"))
      (node (ref "R10") (pin "2") (pinfunction "2_2") (pintype "passive"))
    )
    (net (code "59") (name "Net-(LED2-K)") (class "Default")
      (node (ref "LED2") (pin "2") (pinfunction "K_2") (pintype "passive"))
      (node (ref "U2") (pin "4") (pinfunction "Y_4") (pintype "passive"))
    )
    (net (code "60") (name "Net-(LED3-A)") (class "Default")
      (node (ref "LED3") (pin "1") (pinfunction "A_1") (pintype "passive"))
      (node (ref "R33") (pin "2") (pinfunction "2_2") (pintype "passive"))
    )
    (net (code "61") (name "Net-(LS1--)") (class "Default")
      (node (ref "LS1") (pin "2") (pinfunction "-_2") (pintype "passive"))
      (node (ref "Q2") (pin "D") (pinfunction "D_D") (pintype "passive"))
    )
    (net (code "62") (name "Net-(R33-Pad1)") (class "Default")
      (node (ref "R33") (pin "1") (pinfunction "1_1") (pintype "passive"))
      (node (ref "SJ4") (pin "2") (pinfunction "2_2") (pintype "passive"))
    )
    (net (code "63") (name "Net-(SW1-CH_A)") (class "Default")
      (node (ref "R21") (pin "2") (pinfunction "2_2") (pintype "passive"))
      (node (ref "R25") (pin "1") (pinfunction "1_1") (pintype "passive"))
      (node (ref "SW1") (pin "1") (pinfunction "CH_A_1") (pintype "passive"))
    )
    (net (code "64") (name "Net-(SW1-CH_B)") (class "Default")
      (node (ref "R27") (pin "1") (pinfunction "1_1") (pintype "passive"))
      (node (ref "R28") (pin "1") (pinfunction "1_1") (pintype "passive"))
      (node (ref "SW1") (pin "3") (pinfunction "CH_B_3") (pintype "passive"))
    )
    (net (code "65") (name "Net-(U1-BS)") (class "Default")
      (node (ref "C1") (pin "2") (pinfunction "2_2") (pintype "passive"))
      (node (ref "U1") (pin "1") (pinfunction "BS_1") (pintype "passive"))
    )
    (net (code "66") (name "Net-(U1-EN)") (class "Default")
      (node (ref "R3") (pin "2") (pinfunction "2_2") (pintype "passive"))
      (node (ref "R7") (pin "1") (pinfunction "1_1") (pintype "passive"))
      (node (ref "U1") (pin "4") (pinfunction "EN_4") (pintype "passive"))
    )
    (net (code "67") (name "Net-(U1-FB)") (class "Default")
      (node (ref "C7") (pin "1") (pinfunction "1_1") (pintype "passive"))
      (node (ref "R6") (pin "2") (pinfunction "2_2") (pintype "passive"))
      (node (ref "R8") (pin "2") (pinfunction "2_2") (pintype "passive"))
      (node (ref "U1") (pin "3") (pinfunction "FB_3") (pintype "passive"))
    )
    (net (code "68") (name "Net-(U2A-A)") (class "Default")
      (node (ref "SJ2") (pin "1") (pinfunction "1_1") (pintype "passive"))
      (node (ref "U2") (pin "1") (pinfunction "A_1") (pintype "passive"))
      (node (ref "U2") (pin "2") (pinfunction "B_2") (pintype "passive"))
    )
    (net (code "69") (name "Net-(U3-BYPASS)") (class "Default")
      (node (ref "C14") (pin "2") (pinfunction "2_2") (pintype "passive"))
      (node (ref "U3") (pin "4") (pinfunction "BYPASS_4") (pintype "passive"))
    )
    (net (code "70") (name "Net-(U4-RX)") (class "Default")
      (node (ref "R13") (pin "2") (pinfunction "2_2") (pintype "passive"))
      (node (ref "SJ2") (pin "2") (pinfunction "2_2") (pintype "passive"))
      (node (ref "U4") (pin "3") (pinfunction "RX_3") (pintype "passive"))
    )
    (net (code "71") (name "Net-(U4-TX)") (class "Default")
      (node (ref "R12") (pin "2") (pinfunction "2_2") (pintype "passive"))
      (node (ref "SJ1") (pin "2") (pinfunction "2_2") (pintype "passive"))
      (node (ref "U4") (pin "2") (pinfunction "TX_2") (pintype "passive"))
    )
    (net (code "72") (name "Net-(U4-V3)") (class "Default")
      (node (ref "C16") (pin "2") (pinfunction "2_2") (pintype "passive"))
      (node (ref "U4") (pin "4") (pinfunction "V3_4") (pintype "passive"))
    )
    (net (code "73") (name "Net-(U4-XI)") (class "Default")
      (node (ref "C17") (pin "2") (pinfunction "2_2") (pintype "passive"))
      (node (ref "U4") (pin "7") (pinfunction "XI_7") (pintype "passive"))
      (node (ref "X1") (pin "1") (pinfunction "1_1") (pintype "passive"))
    )
    (net (code "74") (name "Net-(U4-XO)") (class "Default")
      (node (ref "C18") (pin "2") (pinfunction "2_2") (pintype "passive"))
      (node (ref "U4") (pin "8") (pinfunction "XO_8") (pintype "passive"))
      (node (ref "X1") (pin "3") (pinfunction "3_3") (pintype "passive"))
    )
    (net (code "75") (name "Net-(U5-LNA_IN)") (class "Default")
      (node (ref "C9") (pin "2") (pinfunction "2_2") (pintype "passive"))
      (node (ref "L2") (pin "1") (pinfunction "1_1") (pintype "passive"))
      (node (ref "U5") (pin "2") (pinfunction "LNA_IN_2") (pintype "passive"))
    )
    (net (code "76") (name "Net-(U7-C1N)") (class "Default")
      (node (ref "C22") (pin "2") (pinfunction "2_2") (pintype "passive"))
      (node (ref "U7") (pin "5") (pinfunction "C1N_5") (pintype "passive"))
    )
    (net (code "77") (name "Net-(U7-C1P)") (class "Default")
      (node (ref "C22") (pin "1") (pinfunction "1_1") (pintype "passive"))
      (node (ref "U7") (pin "4") (pinfunction "C1P_4") (pintype "passive"))
    )
    (net (code "78") (name "Net-(U7-C2N)") (class "Default")
      (node (ref "C21") (pin "2") (pinfunction "2_2") (pintype "passive"))
      (node (ref "U7") (pin "3") (pinfunction "C2N_3") (pintype "passive"))
    )
    (net (code "79") (name "Net-(U7-C2P)") (class "Default")
      (node (ref "C21") (pin "1") (pinfunction "1_1") (pintype "passive"))
      (node (ref "U7") (pin "2") (pinfunction "C2P_2") (pintype "passive"))
    )
    (net (code "80") (name "Net-(U7-IREF)") (class "Default")
      (node (ref "R29") (pin "2") (pinfunction "2_2") (pintype "passive"))
      (node (ref "U7") (pin "26") (pinfunction "IREF_26") (pintype "passive"))
    )
    (net (code "81") (name "Net-(U7-NC(VBREF))") (class "Default")
      (node (ref "R18") (pin "1") (pinfunction "1_1") (pintype "passive"))
      (node (ref "U7") (pin "7") (pinfunction "NC(VBREF)_7") (pintype "passive"))
    )
    (net (code "82") (name "Net-(U7-VCC)") (class "Default")
      (node (ref "C31") (pin "1") (pinfunction "1_1") (pintype "passive"))
      (node (ref "U7") (pin "28") (pinfunction "VCC_28") (pintype "passive"))
    )
    (net (code "83") (name "Net-(U7-VCOMH)") (class "Default")
      (node (ref "C30") (pin "1") (pinfunction "1_1") (pintype "passive"))
      (node (ref "U7") (pin "27") (pinfunction "VCOMH_27") (pintype "passive"))
    )
    (net (code "84") (name "Net-(USB1-CC1)") (class "Default")
      (node (ref "R5") (pin "1") (pinfunction "1_1") (pintype "passive"))
      (node (ref "USB1") (pin "A5") (pinfunction "CC1_A5") (pintype "passive"))
    )
    (net (code "85") (name "Net-(USB1-CC2)") (class "Default")
      (node (ref "R4") (pin "2") (pinfunction "2_2") (pintype "passive"))
      (node (ref "USB1") (pin "B5") (pinfunction "CC2_B5") (pintype "passive"))
    )
    (net (code "86") (name "VCC") (class "Default")
      (node (ref "C2") (pin "1") (pinfunction "1_1") (pintype "passive"))
      (node (ref "C5") (pin "1") (pinfunction "1_1") (pintype "passive"))
      (node (ref "D1") (pin "2") (pinfunction "C_2") (pintype "passive"))
      (node (ref "D2") (pin "2") (pinfunction "2_2") (pintype "passive"))
      (node (ref "R3") (pin "1") (pinfunction "1_1") (pintype "passive"))
      (node (ref "U1") (pin "5") (pinfunction "IN_5") (pintype "passive"))
    )
    (net (code "87") (name "VCC_3V3") (class "Default")
      (node (ref "C11") (pin "2") (pinfunction "2_2") (pintype "passive"))
      (node (ref "C12") (pin "2") (pinfunction "2_2") (pintype "passive"))
      (node (ref "C20") (pin "1") (pinfunction "1_1") (pintype "passive"))
      (node (ref "C24") (pin "2") (pinfunction "2_2") (pintype "passive"))
      (node (ref "C25") (pin "2") (pinfunction "2_2") (pintype "passive"))
      (node (ref "D7") (pin "2") (pinfunction "C_2") (pintype "passive"))
      (node (ref "LS1") (pin "1") (pinfunction "+_1") (pintype "passive"))
      (node (ref "P3") (pin "1") (pinfunction "1_1") (pintype "passive"))
      (node (ref "P4") (pin "1") (pinfunction "1_1") (pintype "passive"))
      (node (ref "P5") (pin "3") (pinfunction "3_3") (pintype "passive"))
      (node (ref "P6") (pin "3") (pinfunction "3_3") (pintype "passive"))
      (node (ref "R1") (pin "1") (pinfunction "1_1") (pintype "passive"))
      (node (ref "R10") (pin "1") (pinfunction "1_1") (pintype "passive"))
      (node (ref "R19") (pin "2") (pinfunction "2_2") (pintype "passive"))
      (node (ref "R20") (pin "2") (pinfunction "2_2") (pintype "passive"))
      (node (ref "R22") (pin "1") (pinfunction "1_1") (pintype "passive"))
      (node (ref "R23") (pin "1") (pinfunction "1_1") (pintype "passive"))
      (node (ref "R25") (pin "2") (pinfunction "2_2") (pintype "passive"))
      (node (ref "R26") (pin "2") (pinfunction "2_2") (pintype "passive"))
      (node (ref "R27") (pin "2") (pinfunction "2_2") (pintype "passive"))
      (node (ref "R32") (pin "1") (pinfunction "1_1") (pintype "passive"))
      (node (ref "R9") (pin "1") (pinfunction "1_1") (pintype "passive"))
      (node (ref "SJ3") (pin "2") (pinfunction "2_2") (pintype "passive"))
      (node (ref "SJ3") (pin "3") (pinfunction "3_3") (pintype "passive"))
      (node (ref "U2") (pin "5") (pinfunction "VCC_5") (pintype "passive"))
      (node (ref "U3") (pin "5") (pinfunction "VOUT_5") (pintype "passive"))
      (node (ref "U4") (pin "16") (pinfunction "VCC_16") (pintype "passive"))
      (node (ref "U6") (pin "4") (pinfunction "VCC_4") (pintype "power_in"))
      (node (ref "U7") (pin "6") (pinfunction "VBAT_6") (pintype "passive"))
      (node (ref "U7") (pin "9") (pinfunction "VDD_9") (pintype "passive"))
    )
    (net (code "88") (name "VCC_IN") (class "Default")
      (node (ref "D1") (pin "1") (pinfunction "A_1") (pintype "passive"))
      (node (ref "D10") (pin "2") (pinfunction "C_2") (pintype "passive"))
      (node (ref "D9") (pin "2") (pinfunction "C_2") (pintype "passive"))
      (node (ref "P2") (pin "2") (pinfunction "2_2") (pintype "passive"))
      (node (ref "P2") (pin "4") (pinfunction "4_4") (pintype "passive"))
      (node (ref "P7") (pin "1") (pinfunction "1_1") (pintype "passive"))
      (node (ref "P7") (pin "3") (pinfunction "3_3") (pintype "passive"))
      (node (ref "R15") (pin "1") (pinfunction "1_1") (pintype "passive"))
      (node (ref "R31") (pin "1") (pinfunction "1_1") (pintype "passive"))
    )
    (net (code "89") (name "VUSB") (class "Default")
      (node (ref "D3") (pin "1") (pinfunction "A_1") (pintype "passive"))
      (node (ref "USB1") (pin "A4") (pinfunction "VBUS_A4") (pintype "passive"))
      (node (ref "USB1") (pin "A9") (pinfunction "VBUS_A9") (pintype "passive"))
      (node (ref "USB1") (pin "B4") (pinfunction "VBUS_B4") (pintype "passive"))
      (node (ref "USB1") (pin "B9") (pinfunction "VBUS_B9") (pintype "passive"))
    )
    (net (code "90") (name "unconnected-(U4-CTS-Pad9)") (class "Default")
      (node (ref "U4") (pin "9") (pinfunction "CTS_9") (pintype "passive+no_connect"))
    )
    (net (code "91") (name "unconnected-(U4-DCD-Pad12)") (class "Default")
      (node (ref "U4") (pin "12") (pinfunction "DCD_12") (pintype "passive+no_connect"))
    )
    (net (code "92") (name "unconnected-(U4-DSR-Pad10)") (class "Default")
      (node (ref "U4") (pin "10") (pinfunction "DSR_10") (pintype "passive+no_connect"))
    )
    (net (code "93") (name "unconnected-(U4-RI-Pad11)") (class "Default")
      (node (ref "U4") (pin "11") (pinfunction "RI_11") (pintype "passive+no_connect"))
    )
    (net (code "94") (name "unconnected-(U4-RS232-Pad15)") (class "Default")
      (node (ref "U4") (pin "15") (pinfunction "RS232_15") (pintype "passive+no_connect"))
    )
    (net (code "95") (name "unconnected-(U5-CAP1_NC-Pad48)") (class "Default")
      (node (ref "U5") (pin "48") (pinfunction "CAP1_NC_48") (pintype "passive+no_connect"))
    )
    (net (code "96") (name "unconnected-(U5-CAP2_NC-Pad47)") (class "Default")
      (node (ref "U5") (pin "47") (pinfunction "CAP2_NC_47") (pintype "passive+no_connect"))
    )
    (net (code "97") (name "unconnected-(U5-VDD_SDIO_NC-Pad26)") (class "Default")
      (node (ref "U5") (pin "26") (pinfunction "VDD_SDIO_NC_26") (pintype "passive+no_connect"))
    )
    (net (code "98") (name "unconnected-(U5-XTAL_N_NC-Pad44)") (class "Default")
      (node (ref "U5") (pin "44") (pinfunction "XTAL_N_NC_44") (pintype "passive+no_connect"))
    )
    (net (code "99") (name "unconnected-(U5-XTAL_P_NC-Pad45)") (class "Default")
      (node (ref "U5") (pin "45") (pinfunction "XTAL_P_NC_45") (pintype "passive+no_connect"))
    )
    (net (code "100") (name "unconnected-(U6-NC-Pad8)") (class "Default")
      (node (ref "U6") (pin "8") (pinfunction "NC_8") (pintype "passive+no_connect"))
    )
    (net (code "101") (name "unconnected-(USB1-RX1+-PadB11)") (class "Default")
      (node (ref "USB1") (pin "B11") (pinfunction "RX1+_B11") (pintype "passive+no_connect"))
    )
    (net (code "102") (name "unconnected-(USB1-RX1--PadB10)") (class "Default")
      (node (ref "USB1") (pin "B10") (pinfunction "RX1-_B10") (pintype "passive+no_connect"))
    )
    (net (code "103") (name "unconnected-(USB1-RX2+-PadA11)") (class "Default")
      (node (ref "USB1") (pin "A11") (pinfunction "RX2+_A11") (pintype "passive+no_connect"))
    )
    (net (code "104") (name "unconnected-(USB1-RX2--PadA10)") (class "Default")
      (node (ref "USB1") (pin "A10") (pinfunction "RX2-_A10") (pintype "passive+no_connect"))
    )
    (net (code "105") (name "unconnected-(USB1-SBU1-PadA8)") (class "Default")
      (node (ref "USB1") (pin "A8") (pinfunction "SBU1_A8") (pintype "passive+no_connect"))
    )
    (net (code "106") (name "unconnected-(USB1-SBU2-PadB8)") (class "Default")
      (node (ref "USB1") (pin "B8") (pinfunction "SBU2_B8") (pintype "passive+no_connect"))
    )
    (net (code "107") (name "unconnected-(USB1-TX1+-PadA2)") (class "Default")
      (node (ref "USB1") (pin "A2") (pinfunction "TX1+_A2") (pintype "passive+no_connect"))
    )
    (net (code "108") (name "unconnected-(USB1-TX1--PadA3)") (class "Default")
      (node (ref "USB1") (pin "A3") (pinfunction "TX1-_A3") (pintype "passive+no_connect"))
    )
    (net (code "109") (name "unconnected-(USB1-TX2+-PadB2)") (class "Default")
      (node (ref "USB1") (pin "B2") (pinfunction "TX2+_B2") (pintype "passive+no_connect"))
    )
    (net (code "110") (name "unconnected-(USB1-TX2--PadB3)") (class "Default")
      (node (ref "USB1") (pin "B3") (pinfunction "TX2-_B3") (pintype "passive+no_connect"))
    )
  )
)
